# sensor-pod.net
KiCad netlist of a schematic drawn in EAGLE
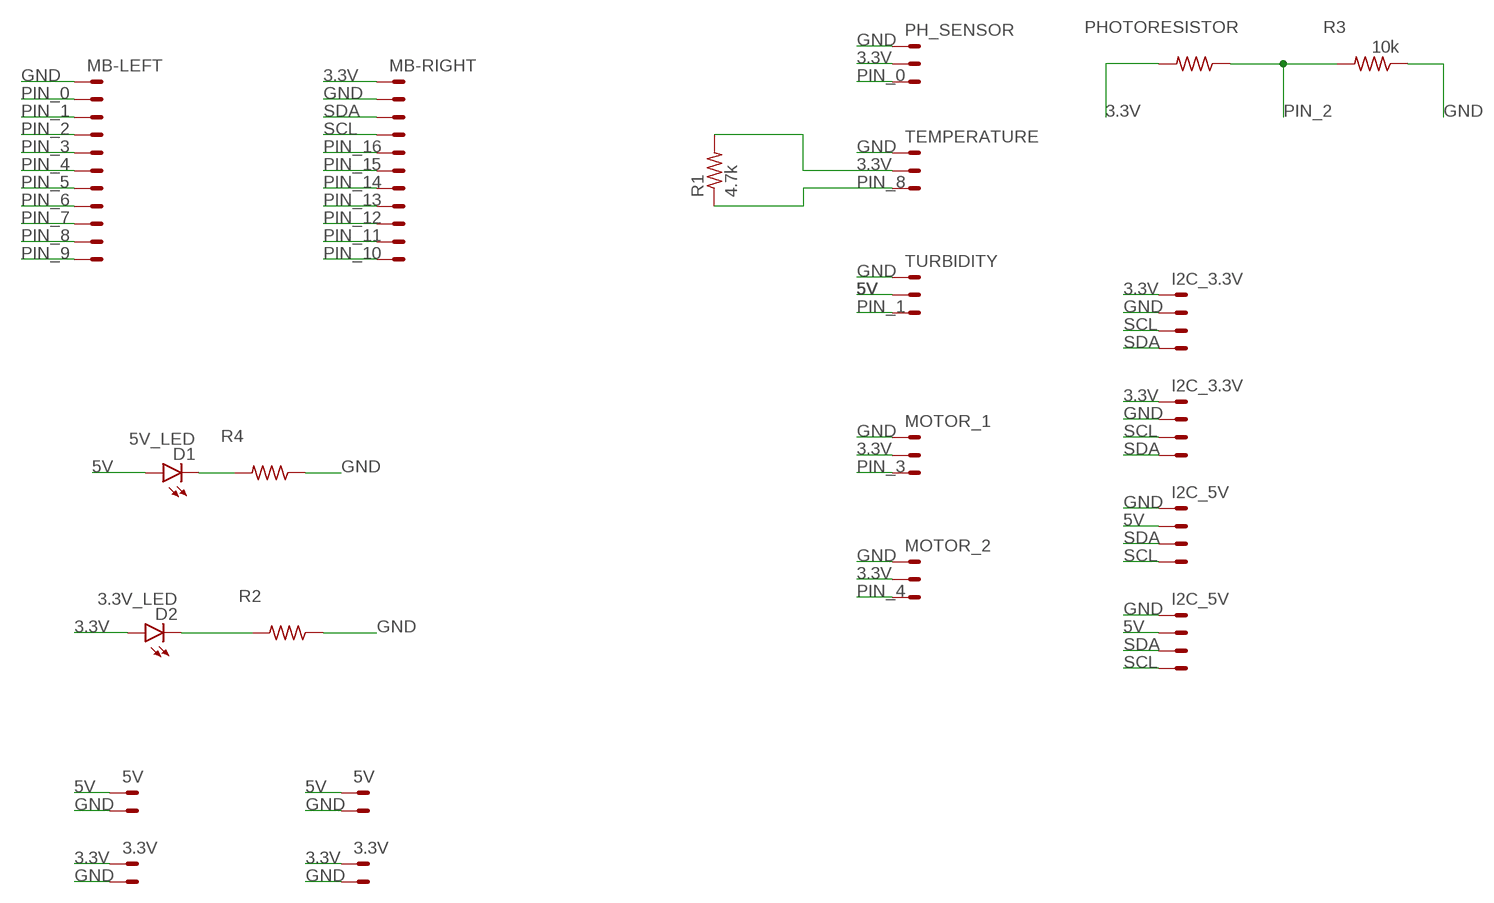
[diagram p0: schematic, sheet 1]

(export (version "E")
  (design (tool "Eeschema 10.0.6"))
  (components
    (comp (ref "1")
      (value "5V")
      (footprint "eagle-import:22-23-2021")
      (fields (field (name "MF") "MOLEX") (field (name "MPN") "22-23-2021"))
      (libsource (lib "eagle-import") (part "22-23-2021"))
    )
    (comp (ref "D1")
      (value "5V_LED")
      (footprint "eagle-import:SFH482")
      (libsource (lib "eagle-import") (part "SFH482"))
    )
    (comp (ref "D2")
      (value "3.3V_LED")
      (footprint "eagle-import:SFH482")
      (libsource (lib "eagle-import") (part "SFH482"))
    )
    (comp (ref "PHOTORESISTOR")
      (value "R-US_0204/7")
      (footprint "eagle-import:0204_7")
      (libsource (lib "eagle-import") (part "R-US_0204/7"))
    )
    (comp (ref "R1")
      (value "4.7k")
      (footprint "eagle-import:0204_7")
      (libsource (lib "eagle-import") (part "R-US_0204/7"))
    )
    (comp (ref "R2")
      (value "R-US_0204/7")
      (footprint "eagle-import:0204_7")
      (libsource (lib "eagle-import") (part "R-US_0204/7"))
    )
    (comp (ref "R3")
      (value "10k")
      (footprint "eagle-import:0204_7")
      (libsource (lib "eagle-import") (part "R-US_0204/7"))
    )
    (comp (ref "R4")
      (value "R-US_0204/7")
      (footprint "eagle-import:0204_7")
      (libsource (lib "eagle-import") (part "R-US_0204/7"))
    )
    (comp (ref "X1")
      (value "PH_SENSOR")
      (footprint "eagle-import:22-23-2031")
      (fields (field (name "MF") "MOLEX") (field (name "MPN") "22-23-2031"))
      (libsource (lib "eagle-import") (part "22-23-2031"))
    )
    (comp (ref "X2")
      (value "I2C_5V")
      (footprint "eagle-import:22-23-2041")
      (fields (field (name "MF") "MOLEX") (field (name "MPN") "22-23-2041"))
      (libsource (lib "eagle-import") (part "22-23-2041"))
    )
    (comp (ref "X3")
      (value "TURBIDITY")
      (footprint "eagle-import:22-23-2031")
      (fields (field (name "MF") "MOLEX") (field (name "MPN") "22-23-2031"))
      (libsource (lib "eagle-import") (part "22-23-2031"))
    )
    (comp (ref "X4")
      (value "5V")
      (footprint "eagle-import:22-23-2021")
      (fields (field (name "MF") "MOLEX") (field (name "MPN") "22-23-2021"))
      (libsource (lib "eagle-import") (part "22-23-2021"))
    )
    (comp (ref "X5")
      (value "TEMPERATURE")
      (footprint "eagle-import:22-23-2031")
      (fields (field (name "MF") "MOLEX") (field (name "MPN") "22-23-2031"))
      (libsource (lib "eagle-import") (part "22-23-2031"))
    )
    (comp (ref "X6")
      (value "MOTOR_1")
      (footprint "eagle-import:22-23-2031")
      (fields (field (name "MF") "MOLEX") (field (name "MPN") "22-23-2031"))
      (libsource (lib "eagle-import") (part "22-23-2031"))
    )
    (comp (ref "X7")
      (value "MOTOR_2")
      (footprint "eagle-import:22-23-2031")
      (fields (field (name "MF") "MOLEX") (field (name "MPN") "22-23-2031"))
      (libsource (lib "eagle-import") (part "22-23-2031"))
    )
    (comp (ref "X8")
      (value "I2C_3.3V")
      (footprint "eagle-import:22-23-2041")
      (fields (field (name "MF") "MOLEX") (field (name "MPN") "22-23-2041"))
      (libsource (lib "eagle-import") (part "22-23-2041"))
    )
    (comp (ref "X9")
      (value "I2C_3.3V")
      (footprint "eagle-import:22-23-2041")
      (fields (field (name "MF") "MOLEX") (field (name "MPN") "22-23-2041"))
      (libsource (lib "eagle-import") (part "22-23-2041"))
    )
    (comp (ref "X10")
      (value "I2C_5V")
      (footprint "eagle-import:22-23-2041")
      (fields (field (name "MF") "MOLEX") (field (name "MPN") "22-23-2041"))
      (libsource (lib "eagle-import") (part "22-23-2041"))
    )
    (comp (ref "X11")
      (value "3.3V")
      (footprint "eagle-import:22-23-2021")
      (fields (field (name "MF") "MOLEX") (field (name "MPN") "22-23-2021"))
      (libsource (lib "eagle-import") (part "22-23-2021"))
    )
    (comp (ref "X12")
      (value "3.3V")
      (footprint "eagle-import:22-23-2021")
      (fields (field (name "MF") "MOLEX") (field (name "MPN") "22-23-2021"))
      (libsource (lib "eagle-import") (part "22-23-2021"))
    )
    (comp (ref "X15")
      (value "MB-LEFT")
      (footprint "eagle-import:22-23-2111")
      (fields (field (name "MF") "MOLEX") (field (name "MPN") "22-23-2111"))
      (libsource (lib "eagle-import") (part "22-23-2111"))
    )
    (comp (ref "X16")
      (value "MB-RIGHT")
      (footprint "eagle-import:22-23-2111")
      (fields (field (name "MF") "MOLEX") (field (name "MPN") "22-23-2111"))
      (libsource (lib "eagle-import") (part "22-23-2111"))
    )
  )
  (nets
    (net (code "1") (name "/3.3V") (class "Default")
      (node (ref "D2") (pin "A") (pinfunction "A_A") (pintype "passive"))
      (node (ref "PHOTORESISTOR") (pin "2") (pinfunction "2_2") (pintype "passive"))
      (node (ref "R1") (pin "2") (pinfunction "2_2") (pintype "passive"))
      (node (ref "X1") (pin "2") (pinfunction "S_2") (pintype "passive"))
      (node (ref "X11") (pin "1") (pinfunction "S_1") (pintype "passive"))
      (node (ref "X12") (pin "1") (pinfunction "S_1") (pintype "passive"))
      (node (ref "X16") (pin "1") (pinfunction "S_1") (pintype "passive"))
      (node (ref "X5") (pin "2") (pinfunction "S_2") (pintype "passive"))
      (node (ref "X6") (pin "2") (pinfunction "S_2") (pintype "passive"))
      (node (ref "X7") (pin "2") (pinfunction "S_2") (pintype "passive"))
      (node (ref "X8") (pin "1") (pinfunction "S_1") (pintype "passive"))
      (node (ref "X9") (pin "1") (pinfunction "S_1") (pintype "passive"))
    )
    (net (code "2") (name "/5V") (class "Default")
      (node (ref "1") (pin "1") (pinfunction "S_1") (pintype "passive"))
      (node (ref "D1") (pin "A") (pinfunction "A_A") (pintype "passive"))
      (node (ref "X10") (pin "2") (pinfunction "S_2") (pintype "passive"))
      (node (ref "X2") (pin "2") (pinfunction "S_2") (pintype "passive"))
      (node (ref "X3") (pin "2") (pinfunction "S_2") (pintype "passive"))
      (node (ref "X4") (pin "1") (pinfunction "S_1") (pintype "passive"))
    )
    (net (code "3") (name "/GND") (class "Default")
      (node (ref "1") (pin "2") (pinfunction "S_2") (pintype "passive"))
      (node (ref "R2") (pin "1") (pinfunction "1_1") (pintype "passive"))
      (node (ref "R3") (pin "1") (pinfunction "1_1") (pintype "passive"))
      (node (ref "R4") (pin "1") (pinfunction "1_1") (pintype "passive"))
      (node (ref "X1") (pin "1") (pinfunction "S_1") (pintype "passive"))
      (node (ref "X10") (pin "1") (pinfunction "S_1") (pintype "passive"))
      (node (ref "X11") (pin "2") (pinfunction "S_2") (pintype "passive"))
      (node (ref "X12") (pin "2") (pinfunction "S_2") (pintype "passive"))
      (node (ref "X15") (pin "1") (pinfunction "S_1") (pintype "passive"))
      (node (ref "X16") (pin "2") (pinfunction "S_2") (pintype "passive"))
      (node (ref "X2") (pin "1") (pinfunction "S_1") (pintype "passive"))
      (node (ref "X3") (pin "1") (pinfunction "S_1") (pintype "passive"))
      (node (ref "X4") (pin "2") (pinfunction "S_2") (pintype "passive"))
      (node (ref "X5") (pin "1") (pinfunction "S_1") (pintype "passive"))
      (node (ref "X6") (pin "1") (pinfunction "S_1") (pintype "passive"))
      (node (ref "X7") (pin "1") (pinfunction "S_1") (pintype "passive"))
      (node (ref "X8") (pin "2") (pinfunction "S_2") (pintype "passive"))
      (node (ref "X9") (pin "2") (pinfunction "S_2") (pintype "passive"))
    )
    (net (code "4") (name "/PIN_0") (class "Default")
      (node (ref "X1") (pin "3") (pinfunction "S_3") (pintype "passive"))
      (node (ref "X15") (pin "2") (pinfunction "S_2") (pintype "passive"))
    )
    (net (code "5") (name "/PIN_1") (class "Default")
      (node (ref "X15") (pin "3") (pinfunction "S_3") (pintype "passive"))
      (node (ref "X3") (pin "3") (pinfunction "S_3") (pintype "passive"))
    )
    (net (code "6") (name "/PIN_2") (class "Default")
      (node (ref "PHOTORESISTOR") (pin "1") (pinfunction "1_1") (pintype "passive"))
      (node (ref "R3") (pin "2") (pinfunction "2_2") (pintype "passive"))
      (node (ref "X15") (pin "4") (pinfunction "S_4") (pintype "passive"))
    )
    (net (code "7") (name "/PIN_3") (class "Default")
      (node (ref "X15") (pin "5") (pinfunction "S_5") (pintype "passive"))
      (node (ref "X6") (pin "3") (pinfunction "S_3") (pintype "passive"))
    )
    (net (code "8") (name "/PIN_4") (class "Default")
      (node (ref "X15") (pin "6") (pinfunction "S_6") (pintype "passive"))
      (node (ref "X7") (pin "3") (pinfunction "S_3") (pintype "passive"))
    )
    (net (code "9") (name "/PIN_5") (class "Default")
      (node (ref "X15") (pin "7") (pinfunction "S_7") (pintype "passive"))
    )
    (net (code "10") (name "/PIN_6") (class "Default")
      (node (ref "X15") (pin "8") (pinfunction "S_8") (pintype "passive"))
    )
    (net (code "11") (name "/PIN_7") (class "Default")
      (node (ref "X15") (pin "9") (pinfunction "S_9") (pintype "passive"))
    )
    (net (code "12") (name "/PIN_8") (class "Default")
      (node (ref "R1") (pin "1") (pinfunction "1_1") (pintype "passive"))
      (node (ref "X15") (pin "10") (pinfunction "S_10") (pintype "passive"))
      (node (ref "X5") (pin "3") (pinfunction "S_3") (pintype "passive"))
    )
    (net (code "13") (name "/PIN_9") (class "Default")
      (node (ref "X15") (pin "11") (pinfunction "S_11") (pintype "passive"))
    )
    (net (code "14") (name "/PIN_10") (class "Default")
      (node (ref "X16") (pin "11") (pinfunction "S_11") (pintype "passive"))
    )
    (net (code "15") (name "/PIN_11") (class "Default")
      (node (ref "X16") (pin "10") (pinfunction "S_10") (pintype "passive"))
    )
    (net (code "16") (name "/PIN_12") (class "Default")
      (node (ref "X16") (pin "9") (pinfunction "S_9") (pintype "passive"))
    )
    (net (code "17") (name "/PIN_13") (class "Default")
      (node (ref "X16") (pin "8") (pinfunction "S_8") (pintype "passive"))
    )
    (net (code "18") (name "/PIN_14") (class "Default")
      (node (ref "X16") (pin "7") (pinfunction "S_7") (pintype "passive"))
    )
    (net (code "19") (name "/PIN_15") (class "Default")
      (node (ref "X16") (pin "6") (pinfunction "S_6") (pintype "passive"))
    )
    (net (code "20") (name "/PIN_16") (class "Default")
      (node (ref "X16") (pin "5") (pinfunction "S_5") (pintype "passive"))
    )
    (net (code "21") (name "/SCL") (class "Default")
      (node (ref "X10") (pin "4") (pinfunction "S_4") (pintype "passive"))
      (node (ref "X16") (pin "4") (pinfunction "S_4") (pintype "passive"))
      (node (ref "X2") (pin "4") (pinfunction "S_4") (pintype "passive"))
      (node (ref "X8") (pin "3") (pinfunction "S_3") (pintype "passive"))
      (node (ref "X9") (pin "3") (pinfunction "S_3") (pintype "passive"))
    )
    (net (code "22") (name "/SDA") (class "Default")
      (node (ref "X10") (pin "3") (pinfunction "S_3") (pintype "passive"))
      (node (ref "X16") (pin "3") (pinfunction "S_3") (pintype "passive"))
      (node (ref "X2") (pin "3") (pinfunction "S_3") (pintype "passive"))
      (node (ref "X8") (pin "4") (pinfunction "S_4") (pintype "passive"))
      (node (ref "X9") (pin "4") (pinfunction "S_4") (pintype "passive"))
    )
    (net (code "23") (name "Net-(D1-C)") (class "Default")
      (node (ref "D1") (pin "K") (pinfunction "C_K") (pintype "passive"))
      (node (ref "R4") (pin "2") (pinfunction "2_2") (pintype "passive"))
    )
    (net (code "24") (name "Net-(D2-C)") (class "Default")
      (node (ref "D2") (pin "K") (pinfunction "C_K") (pintype "passive"))
      (node (ref "R2") (pin "2") (pinfunction "2_2") (pintype "passive"))
    )
  )
)
